# sim800V2.net
KiCad netlist of a schematic drawn in EAGLE
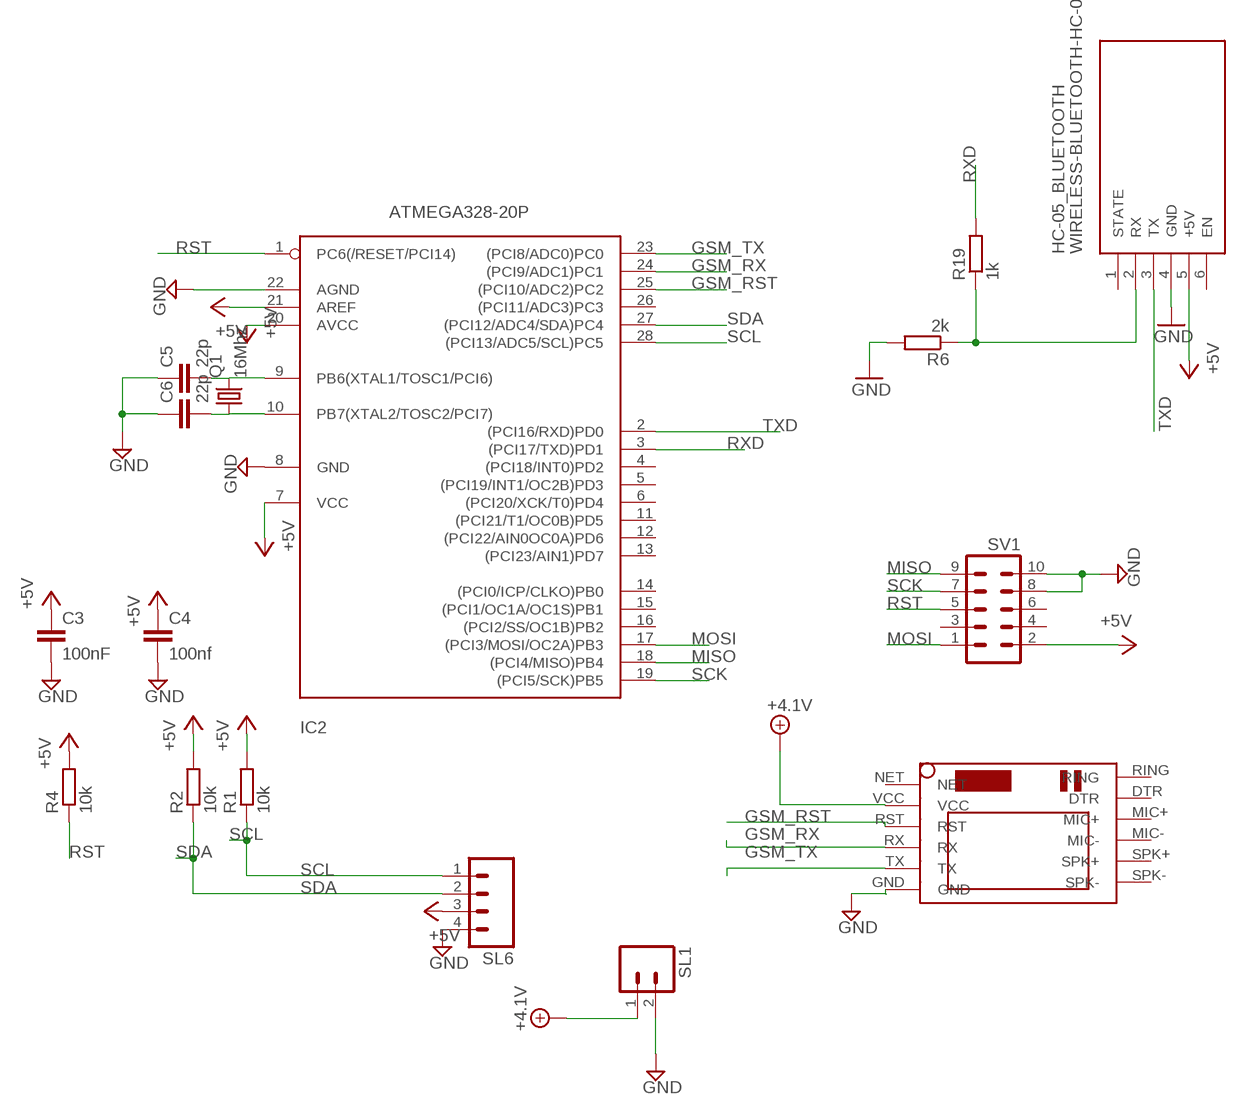
[diagram p0: schematic, sheet 1]
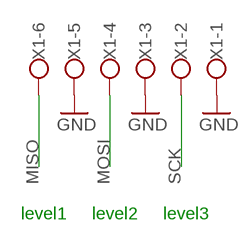
[diagram p1: schematic, sheet 2]
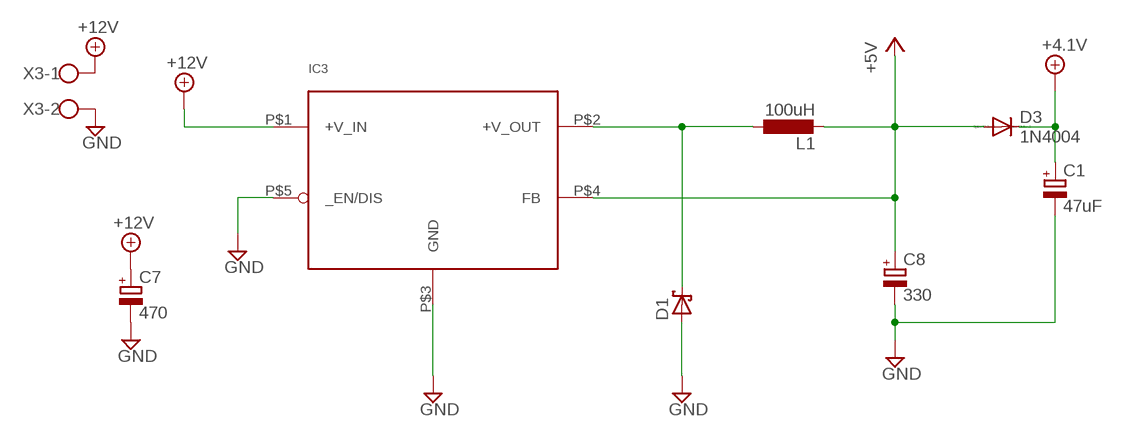
[diagram p2: schematic, sheet 3]

(export (version "E")
  (design (tool "Eeschema 10.0.6"))
  (components
    (comp (ref "C3")
      (value "100nF")
      (footprint "eagle-import:C050-025X075")
      (libsource (lib "eagle-import") (part "C-EU050-025X075"))
    )
    (comp (ref "C4")
      (value "100nf")
      (footprint "eagle-import:C050-025X075")
      (libsource (lib "eagle-import") (part "C-EU050-025X075"))
    )
    (comp (ref "C5")
      (value "22p")
      (footprint "eagle-import:C025-025X050")
      (libsource (lib "eagle-import") (part "C-EU025-025X050"))
    )
    (comp (ref "C6")
      (value "22p")
      (footprint "eagle-import:C025-025X050")
      (libsource (lib "eagle-import") (part "C-EU025-025X050"))
    )
    (comp (ref "HC-05_BLUETOOTH")
      (value "WIRELESS-BLUETOOTH-HC-05")
      (footprint "eagle-import:WIRELESS-BLUETOOTH-HC-05")
      (libsource (lib "eagle-import") (part "WIRELESS-BLUETOOTH-HC-05"))
    )
    (comp (ref "IC2")
      (value "ATMEGA328-20P")
      (footprint "eagle-import:DIL28-3")
      (libsource (lib "eagle-import") (part "ATMEGA328P-20"))
    )
    (comp (ref "Q1")
      (value "16Mhz")
      (footprint "eagle-import:HC49U-V")
      (libsource (lib "eagle-import") (part "CRYSTALHC49U-V"))
    )
    (comp (ref "R1")
      (value "10k")
      (footprint "eagle-import:0207_10")
      (libsource (lib "eagle-import") (part "rcl_334_R-EU_0207/10"))
    )
    (comp (ref "R2")
      (value "10k")
      (footprint "eagle-import:0207_10")
      (libsource (lib "eagle-import") (part "rcl_334_R-EU_0207/10"))
    )
    (comp (ref "R4")
      (value "10k")
      (footprint "eagle-import:0207_10")
      (libsource (lib "eagle-import") (part "rcl_334_R-EU_0207/10"))
    )
    (comp (ref "R6")
      (value "2k")
      (footprint "eagle-import:R0805")
      (libsource (lib "eagle-import") (part "R-EU_R0805"))
    )
    (comp (ref "R19")
      (value "1k")
      (footprint "eagle-import:R0805")
      (libsource (lib "eagle-import") (part "R-EU_R0805"))
    )
    (comp (ref "SL1")
      (value "M02")
      (footprint "eagle-import:02P")
      (libsource (lib "eagle-import") (part "M02"))
    )
    (comp (ref "SL6")
      (value "M04")
      (footprint "eagle-import:04P")
      (libsource (lib "eagle-import") (part "M04"))
    )
    (comp (ref "SV1")
      (value "ML10")
      (footprint "eagle-import:ML10")
      (libsource (lib "eagle-import") (part "ML10"))
    )
    (comp (ref "U$1")
      (value "SIM800LMODULE")
      (footprint "eagle-import:SIM800LMODULE")
      (libsource (lib "eagle-import") (part "SIM800LMODULE"))
    )
    (comp (ref "C1")
      (value "47uF")
      (footprint "eagle-import:E2,5-6")
      (libsource (lib "eagle-import") (part "rcl_334_CPOL-EUE2.5-6"))
    )
    (comp (ref "C7")
      (value "470")
      (footprint "eagle-import:E3,5-8")
      (libsource (lib "eagle-import") (part "CPOL-EUE3.5-8"))
    )
    (comp (ref "C8")
      (value "330")
      (footprint "eagle-import:E3,5-8")
      (libsource (lib "eagle-import") (part "CPOL-EUE3.5-8"))
    )
    (comp (ref "D1")
      (value "SCHOTTKY-DIODESMD")
      (footprint "eagle-import:SMB")
      (libsource (lib "eagle-import") (part "SCHOTTKY-DIODESMD"))
    )
    (comp (ref "D3")
      (value "1N4004")
      (footprint "eagle-import:DO41-10")
      (libsource (lib "eagle-import") (part "1N4004"))
    )
    (comp (ref "IC3")
      (value "LM2576-T05D")
      (footprint "eagle-import:TO220-5_STAGGERED")
      (libsource (lib "eagle-import") (part "LM2576-T05D"))
    )
    (comp (ref "L1")
      (value "100uH")
      (footprint "eagle-import:6000-XXXX-RC")
      (libsource (lib "eagle-import") (part "L-EU6000-XXX-RC"))
    )
    (comp (ref "X3")
      (value "W237-102")
      (footprint "eagle-import:W237-102")
      (fields (field (name "MPN") "237-102"))
      (libsource (lib "eagle-import") (part "W237-102"))
    )
    (comp (ref "X1")
      (value "W237-136")
      (footprint "eagle-import:W237-136")
      (fields (field (name "MPN") "237-136"))
      (libsource (lib "eagle-import") (part "W237-136"))
    )
  )
  (nets
    (net (code "1") (name "+4.1V") (class "Default")
      (node (ref "C1") (pin "+") (pinfunction "+_+") (pintype "passive"))
      (node (ref "D3") (pin "C") (pinfunction "C_C") (pintype "passive"))
      (node (ref "SL1") (pin "1") (pinfunction "1_1") (pintype "passive"))
      (node (ref "U$1") (pin "VCC") (pinfunction "VCC_VCC") (pintype "bidirectional"))
    )
    (net (code "2") (name "+5V") (class "Default")
      (node (ref "C3") (pin "1") (pinfunction "1_1") (pintype "passive"))
      (node (ref "C4") (pin "1") (pinfunction "1_1") (pintype "passive"))
      (node (ref "C8") (pin "+") (pinfunction "+_+") (pintype "passive"))
      (node (ref "D3") (pin "A") (pinfunction "A_A") (pintype "passive"))
      (node (ref "HC-05_BLUETOOTH") (pin "5") (pinfunction "+5V_5") (pintype "power_in"))
      (node (ref "IC2") (pin "20") (pinfunction "AVCC_20") (pintype "bidirectional"))
      (node (ref "IC2") (pin "21") (pinfunction "AREF_21") (pintype "bidirectional"))
      (node (ref "IC2") (pin "7") (pinfunction "VCC_7") (pintype "bidirectional"))
      (node (ref "IC3") (pin "P$4") (pinfunction "FB_P$4") (pintype "input"))
      (node (ref "L1") (pin "2") (pinfunction "2_2") (pintype "passive"))
      (node (ref "R1") (pin "2") (pinfunction "2_2") (pintype "passive"))
      (node (ref "R2") (pin "2") (pinfunction "2_2") (pintype "passive"))
      (node (ref "R4") (pin "2") (pinfunction "2_2") (pintype "passive"))
      (node (ref "SL6") (pin "3") (pinfunction "3_3") (pintype "passive"))
      (node (ref "SV1") (pin "2") (pinfunction "2_2") (pintype "passive"))
    )
    (net (code "3") (name "+12V") (class "Default")
      (node (ref "C7") (pin "+") (pinfunction "+_+") (pintype "passive"))
      (node (ref "IC3") (pin "P$1") (pinfunction "+V_IN_P$1") (pintype "input"))
      (node (ref "X3") (pin "1") (pinfunction "KL_1") (pintype "passive"))
    )
    (net (code "4") (name "GND") (class "Default")
      (node (ref "C1") (pin "-") (pinfunction "-_-") (pintype "passive"))
      (node (ref "C3") (pin "2") (pinfunction "2_2") (pintype "passive"))
      (node (ref "C4") (pin "2") (pinfunction "2_2") (pintype "passive"))
      (node (ref "C5") (pin "1") (pinfunction "1_1") (pintype "passive"))
      (node (ref "C6") (pin "1") (pinfunction "1_1") (pintype "passive"))
      (node (ref "C7") (pin "-") (pinfunction "-_-") (pintype "passive"))
      (node (ref "C8") (pin "-") (pinfunction "-_-") (pintype "passive"))
      (node (ref "D1") (pin "A") (pinfunction "A_A") (pintype "passive"))
      (node (ref "HC-05_BLUETOOTH") (pin "4") (pinfunction "GND_4") (pintype "power_in"))
      (node (ref "IC2") (pin "22") (pinfunction "AGND_22") (pintype "bidirectional"))
      (node (ref "IC2") (pin "8") (pinfunction "GND_8") (pintype "bidirectional"))
      (node (ref "IC3") (pin "P$3") (pinfunction "GND_P$3") (pintype "power_in"))
      (node (ref "IC3") (pin "P$5") (pinfunction "_EN/DIS_P$5") (pintype "input"))
      (node (ref "R6") (pin "2") (pinfunction "2_2") (pintype "passive"))
      (node (ref "SL1") (pin "2") (pinfunction "2_2") (pintype "passive"))
      (node (ref "SL6") (pin "4") (pinfunction "4_4") (pintype "passive"))
      (node (ref "SV1") (pin "10") (pinfunction "10_10") (pintype "passive"))
      (node (ref "SV1") (pin "8") (pinfunction "8_8") (pintype "passive"))
      (node (ref "U$1") (pin "GND") (pinfunction "GND_GND") (pintype "bidirectional"))
      (node (ref "X1") (pin "1") (pinfunction "KL_1") (pintype "passive"))
      (node (ref "X1") (pin "3") (pinfunction "KL_3") (pintype "passive"))
      (node (ref "X1") (pin "5") (pinfunction "KL_5") (pintype "passive"))
      (node (ref "X3") (pin "2") (pinfunction "KL_2") (pintype "passive"))
    )
    (net (code "5") (name "GSM_RST") (class "Default")
      (node (ref "IC2") (pin "25") (pinfunction "(PCI10/ADC2)PC2_25") (pintype "bidirectional"))
      (node (ref "U$1") (pin "RST") (pinfunction "RST_RST") (pintype "bidirectional"))
    )
    (net (code "6") (name "GSM_RX") (class "Default")
      (node (ref "IC2") (pin "24") (pinfunction "(PCI9/ADC1)PC1_24") (pintype "bidirectional"))
      (node (ref "U$1") (pin "RX") (pinfunction "RX_RX") (pintype "bidirectional"))
    )
    (net (code "7") (name "GSM_TX") (class "Default")
      (node (ref "IC2") (pin "23") (pinfunction "(PCI8/ADC0)PC0_23") (pintype "bidirectional"))
      (node (ref "U$1") (pin "TX") (pinfunction "TX_TX") (pintype "bidirectional"))
    )
    (net (code "8") (name "MISO") (class "Default")
      (node (ref "IC2") (pin "18") (pinfunction "(PCI4/MISO)PB4_18") (pintype "bidirectional"))
      (node (ref "SV1") (pin "9") (pinfunction "9_9") (pintype "passive"))
      (node (ref "X1") (pin "6") (pinfunction "KL_6") (pintype "passive"))
    )
    (net (code "9") (name "MOSI") (class "Default")
      (node (ref "IC2") (pin "17") (pinfunction "(PCI3/MOSI/OC2A)PB3_17") (pintype "bidirectional"))
      (node (ref "SV1") (pin "1") (pinfunction "1_1") (pintype "passive"))
      (node (ref "X1") (pin "4") (pinfunction "KL_4") (pintype "passive"))
    )
    (net (code "10") (name "Net-(HC-05_BLUETOOTH-RX)") (class "Default")
      (node (ref "HC-05_BLUETOOTH") (pin "2") (pinfunction "RX_2") (pintype "bidirectional"))
      (node (ref "R19") (pin "1") (pinfunction "1_1") (pintype "passive"))
      (node (ref "R6") (pin "1") (pinfunction "1_1") (pintype "passive"))
    )
    (net (code "11") (name "Net-(IC2-PB6(XTAL1{slash}TOSC1{slash}PCI6))") (class "Default")
      (node (ref "C5") (pin "2") (pinfunction "2_2") (pintype "passive"))
      (node (ref "IC2") (pin "9") (pinfunction "PB6(XTAL1/TOSC1/PCI6)_9") (pintype "bidirectional"))
      (node (ref "Q1") (pin "2") (pinfunction "2_2") (pintype "passive"))
    )
    (net (code "12") (name "Net-(IC2-PB7(XTAL2{slash}TOSC2{slash}PCI7))") (class "Default")
      (node (ref "C6") (pin "2") (pinfunction "2_2") (pintype "passive"))
      (node (ref "IC2") (pin "10") (pinfunction "PB7(XTAL2/TOSC2/PCI7)_10") (pintype "bidirectional"))
      (node (ref "Q1") (pin "1") (pinfunction "1_1") (pintype "passive"))
    )
    (net (code "13") (name "Net-(IC3-+V_OUT)") (class "Default")
      (node (ref "D1") (pin "C") (pinfunction "C_C") (pintype "passive"))
      (node (ref "IC3") (pin "P$2") (pinfunction "+V_OUT_P$2") (pintype "output"))
      (node (ref "L1") (pin "1") (pinfunction "1_1") (pintype "passive"))
    )
    (net (code "14") (name "RST") (class "Default")
      (node (ref "IC2") (pin "1") (pinfunction "PC6(/RESET/PCI14)_1") (pintype "bidirectional"))
      (node (ref "R4") (pin "1") (pinfunction "1_1") (pintype "passive"))
      (node (ref "SV1") (pin "5") (pinfunction "5_5") (pintype "passive"))
    )
    (net (code "15") (name "RXD") (class "Default")
      (node (ref "IC2") (pin "3") (pinfunction "(PCI17/TXD)PD1_3") (pintype "bidirectional"))
      (node (ref "R19") (pin "2") (pinfunction "2_2") (pintype "passive"))
    )
    (net (code "16") (name "SCK") (class "Default")
      (node (ref "IC2") (pin "19") (pinfunction "(PCI5/SCK)PB5_19") (pintype "bidirectional"))
      (node (ref "SV1") (pin "7") (pinfunction "7_7") (pintype "passive"))
      (node (ref "X1") (pin "2") (pinfunction "KL_2") (pintype "passive"))
    )
    (net (code "17") (name "SCL") (class "Default")
      (node (ref "IC2") (pin "28") (pinfunction "(PCI13/ADC5/SCL)PC5_28") (pintype "bidirectional"))
      (node (ref "R1") (pin "1") (pinfunction "1_1") (pintype "passive"))
      (node (ref "SL6") (pin "1") (pinfunction "1_1") (pintype "passive"))
    )
    (net (code "18") (name "SDA") (class "Default")
      (node (ref "IC2") (pin "27") (pinfunction "(PCI12/ADC4/SDA)PC4_27") (pintype "bidirectional"))
      (node (ref "R2") (pin "1") (pinfunction "1_1") (pintype "passive"))
      (node (ref "SL6") (pin "2") (pinfunction "2_2") (pintype "passive"))
    )
    (net (code "19") (name "TXD") (class "Default")
      (node (ref "HC-05_BLUETOOTH") (pin "3") (pinfunction "TX_3") (pintype "bidirectional"))
      (node (ref "IC2") (pin "2") (pinfunction "(PCI16/RXD)PD0_2") (pintype "bidirectional"))
    )
    (net (code "20") (name "unconnected-(HC-05_BLUETOOTH-EN-Pad6)") (class "Default")
      (node (ref "HC-05_BLUETOOTH") (pin "6") (pinfunction "EN_6") (pintype "bidirectional"))
    )
    (net (code "21") (name "unconnected-(HC-05_BLUETOOTH-STATE-Pad1)") (class "Default")
      (node (ref "HC-05_BLUETOOTH") (pin "1") (pinfunction "STATE_1") (pintype "bidirectional"))
    )
    (net (code "22") (name "unconnected-(IC2-(PCI0{slash}ICP{slash}CLKO)PB0-Pad14)") (class "Default")
      (node (ref "IC2") (pin "14") (pinfunction "(PCI0/ICP/CLKO)PB0_14") (pintype "bidirectional"))
    )
    (net (code "23") (name "unconnected-(IC2-(PCI1{slash}OC1A{slash}OC1S)PB1-Pad15)") (class "Default")
      (node (ref "IC2") (pin "15") (pinfunction "(PCI1/OC1A/OC1S)PB1_15") (pintype "bidirectional"))
    )
    (net (code "24") (name "unconnected-(IC2-(PCI2{slash}SS{slash}OC1B)PB2-Pad16)") (class "Default")
      (node (ref "IC2") (pin "16") (pinfunction "(PCI2/SS/OC1B)PB2_16") (pintype "bidirectional"))
    )
    (net (code "25") (name "unconnected-(IC2-(PCI11{slash}ADC3)PC3-Pad26)") (class "Default")
      (node (ref "IC2") (pin "26") (pinfunction "(PCI11/ADC3)PC3_26") (pintype "bidirectional"))
    )
    (net (code "26") (name "unconnected-(IC2-(PCI18{slash}INT0)PD2-Pad4)") (class "Default")
      (node (ref "IC2") (pin "4") (pinfunction "(PCI18/INT0)PD2_4") (pintype "bidirectional"))
    )
    (net (code "27") (name "unconnected-(IC2-(PCI19{slash}INT1{slash}OC2B)PD3-Pad5)") (class "Default")
      (node (ref "IC2") (pin "5") (pinfunction "(PCI19/INT1/OC2B)PD3_5") (pintype "bidirectional"))
    )
    (net (code "28") (name "unconnected-(IC2-(PCI20{slash}XCK{slash}T0)PD4-Pad6)") (class "Default")
      (node (ref "IC2") (pin "6") (pinfunction "(PCI20/XCK/T0)PD4_6") (pintype "bidirectional"))
    )
    (net (code "29") (name "unconnected-(IC2-(PCI21{slash}T1{slash}OC0B)PD5-Pad11)") (class "Default")
      (node (ref "IC2") (pin "11") (pinfunction "(PCI21/T1/OC0B)PD5_11") (pintype "bidirectional"))
    )
    (net (code "30") (name "unconnected-(IC2-(PCI22{slash}AIN0OC0A)PD6-Pad12)") (class "Default")
      (node (ref "IC2") (pin "12") (pinfunction "(PCI22/AIN0OC0A)PD6_12") (pintype "bidirectional"))
    )
    (net (code "31") (name "unconnected-(IC2-(PCI23{slash}AIN1)PD7-Pad13)") (class "Default")
      (node (ref "IC2") (pin "13") (pinfunction "(PCI23/AIN1)PD7_13") (pintype "bidirectional"))
    )
    (net (code "32") (name "unconnected-(SV1-Pad3)") (class "Default")
      (node (ref "SV1") (pin "3") (pinfunction "3_3") (pintype "passive"))
    )
    (net (code "33") (name "unconnected-(SV1-Pad4)") (class "Default")
      (node (ref "SV1") (pin "4") (pinfunction "4_4") (pintype "passive"))
    )
    (net (code "34") (name "unconnected-(SV1-Pad6)") (class "Default")
      (node (ref "SV1") (pin "6") (pinfunction "6_6") (pintype "passive"))
    )
    (net (code "35") (name "unconnected-(U$1-PadDTR)") (class "Default")
      (node (ref "U$1") (pin "DTR") (pinfunction "DTR_DTR") (pintype "bidirectional"))
    )
    (net (code "36") (name "unconnected-(U$1-PadMIC+)") (class "Default")
      (node (ref "U$1") (pin "MIC+") (pinfunction "MIC+_MIC+") (pintype "bidirectional"))
    )
    (net (code "37") (name "unconnected-(U$1-PadMIC-)") (class "Default")
      (node (ref "U$1") (pin "MIC-") (pinfunction "MIC-_MIC-") (pintype "bidirectional"))
    )
    (net (code "38") (name "unconnected-(U$1-PadNET)") (class "Default")
      (node (ref "U$1") (pin "NET") (pinfunction "NET_NET") (pintype "bidirectional"))
    )
    (net (code "39") (name "unconnected-(U$1-PadRING)") (class "Default")
      (node (ref "U$1") (pin "RING") (pinfunction "RING_RING") (pintype "bidirectional"))
    )
    (net (code "40") (name "unconnected-(U$1-PadSPK+)") (class "Default")
      (node (ref "U$1") (pin "SPK+") (pinfunction "SPK+_SPK+") (pintype "bidirectional"))
    )
    (net (code "41") (name "unconnected-(U$1-PadSPK-)") (class "Default")
      (node (ref "U$1") (pin "SPK-") (pinfunction "SPK-_SPK-") (pintype "bidirectional"))
    )
  )
)
